# schema_evaluatie_week_5.net
KiCad netlist of a schematic drawn in EAGLE
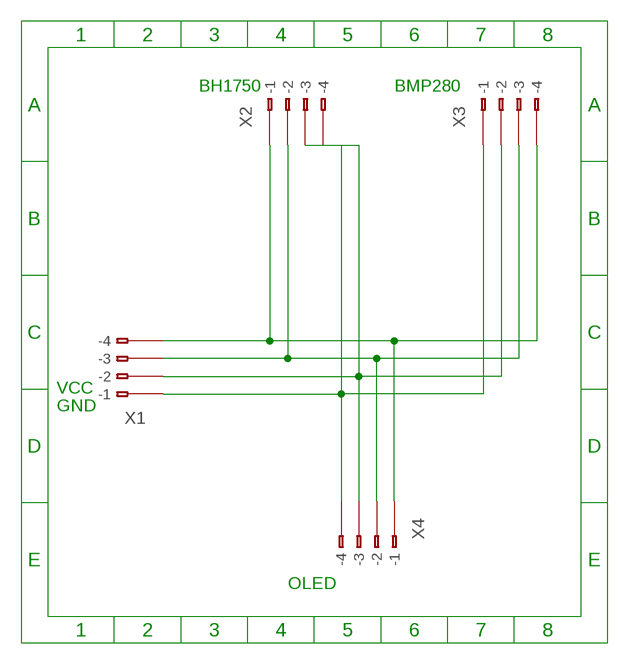
[diagram p0: schematic, sheet 1]

(export (version "E")
  (design (tool "Eeschema 10.0.6"))
  (components
    (comp (ref "X1")
      (value "233-104")
      (footprint "eagle-import:233-104")
      (libsource (lib "eagle-import") (part "233-104"))
    )
    (comp (ref "X2")
      (value "233-104")
      (footprint "eagle-import:233-104")
      (libsource (lib "eagle-import") (part "233-104"))
    )
    (comp (ref "X3")
      (value "233-104")
      (footprint "eagle-import:233-104")
      (libsource (lib "eagle-import") (part "233-104"))
    )
    (comp (ref "X4")
      (value "233-104")
      (footprint "eagle-import:233-104")
      (libsource (lib "eagle-import") (part "233-104"))
    )
  )
  (nets
    (net (code "1") (name "Net-(X1-B-1)") (class "Default")
      (node (ref "X1") (pin "B1") (pinfunction "B-1_B1") (pintype "passive"))
      (node (ref "X2") (pin "B3") (pinfunction "B-3_B3") (pintype "passive"))
      (node (ref "X3") (pin "B1") (pinfunction "B-1_B1") (pintype "passive"))
      (node (ref "X4") (pin "B4") (pinfunction "B-4_B4") (pintype "passive"))
    )
    (net (code "2") (name "Net-(X1-B-2)") (class "Default")
      (node (ref "X1") (pin "B2") (pinfunction "B-2_B2") (pintype "passive"))
      (node (ref "X2") (pin "B4") (pinfunction "B-4_B4") (pintype "passive"))
      (node (ref "X3") (pin "B2") (pinfunction "B-2_B2") (pintype "passive"))
      (node (ref "X4") (pin "B3") (pinfunction "B-3_B3") (pintype "passive"))
    )
    (net (code "3") (name "Net-(X1-B-3)") (class "Default")
      (node (ref "X1") (pin "B3") (pinfunction "B-3_B3") (pintype "passive"))
      (node (ref "X2") (pin "B2") (pinfunction "B-2_B2") (pintype "passive"))
      (node (ref "X3") (pin "B3") (pinfunction "B-3_B3") (pintype "passive"))
      (node (ref "X4") (pin "B2") (pinfunction "B-2_B2") (pintype "passive"))
    )
    (net (code "4") (name "Net-(X1-B-4)") (class "Default")
      (node (ref "X1") (pin "B4") (pinfunction "B-4_B4") (pintype "passive"))
      (node (ref "X2") (pin "B1") (pinfunction "B-1_B1") (pintype "passive"))
      (node (ref "X3") (pin "B4") (pinfunction "B-4_B4") (pintype "passive"))
      (node (ref "X4") (pin "B1") (pinfunction "B-1_B1") (pintype "passive"))
    )
    (net (code "5") (name "unconnected-(X1--1-PadA1)") (class "Default")
      (node (ref "X1") (pin "A1") (pinfunction "-1_A1") (pintype "passive"))
    )
    (net (code "6") (name "unconnected-(X1--2-PadA2)") (class "Default")
      (node (ref "X1") (pin "A2") (pinfunction "-2_A2") (pintype "passive"))
    )
    (net (code "7") (name "unconnected-(X1--3-PadA3)") (class "Default")
      (node (ref "X1") (pin "A3") (pinfunction "-3_A3") (pintype "passive"))
    )
    (net (code "8") (name "unconnected-(X1--4-PadA4)") (class "Default")
      (node (ref "X1") (pin "A4") (pinfunction "-4_A4") (pintype "passive"))
    )
    (net (code "9") (name "unconnected-(X2--1-PadA1)") (class "Default")
      (node (ref "X2") (pin "A1") (pinfunction "-1_A1") (pintype "passive"))
    )
    (net (code "10") (name "unconnected-(X2--2-PadA2)") (class "Default")
      (node (ref "X2") (pin "A2") (pinfunction "-2_A2") (pintype "passive"))
    )
    (net (code "11") (name "unconnected-(X2--3-PadA3)") (class "Default")
      (node (ref "X2") (pin "A3") (pinfunction "-3_A3") (pintype "passive"))
    )
    (net (code "12") (name "unconnected-(X2--4-PadA4)") (class "Default")
      (node (ref "X2") (pin "A4") (pinfunction "-4_A4") (pintype "passive"))
    )
    (net (code "13") (name "unconnected-(X3--1-PadA1)") (class "Default")
      (node (ref "X3") (pin "A1") (pinfunction "-1_A1") (pintype "passive"))
    )
    (net (code "14") (name "unconnected-(X3--2-PadA2)") (class "Default")
      (node (ref "X3") (pin "A2") (pinfunction "-2_A2") (pintype "passive"))
    )
    (net (code "15") (name "unconnected-(X3--3-PadA3)") (class "Default")
      (node (ref "X3") (pin "A3") (pinfunction "-3_A3") (pintype "passive"))
    )
    (net (code "16") (name "unconnected-(X3--4-PadA4)") (class "Default")
      (node (ref "X3") (pin "A4") (pinfunction "-4_A4") (pintype "passive"))
    )
    (net (code "17") (name "unconnected-(X4--1-PadA1)") (class "Default")
      (node (ref "X4") (pin "A1") (pinfunction "-1_A1") (pintype "passive"))
    )
    (net (code "18") (name "unconnected-(X4--2-PadA2)") (class "Default")
      (node (ref "X4") (pin "A2") (pinfunction "-2_A2") (pintype "passive"))
    )
    (net (code "19") (name "unconnected-(X4--3-PadA3)") (class "Default")
      (node (ref "X4") (pin "A3") (pinfunction "-3_A3") (pintype "passive"))
    )
    (net (code "20") (name "unconnected-(X4--4-PadA4)") (class "Default")
      (node (ref "X4") (pin "A4") (pinfunction "-4_A4") (pintype "passive"))
    )
  )
)
